# Page12_SOM_Interface.net
KiCad netlist of a schematic drawn in Altium Designer
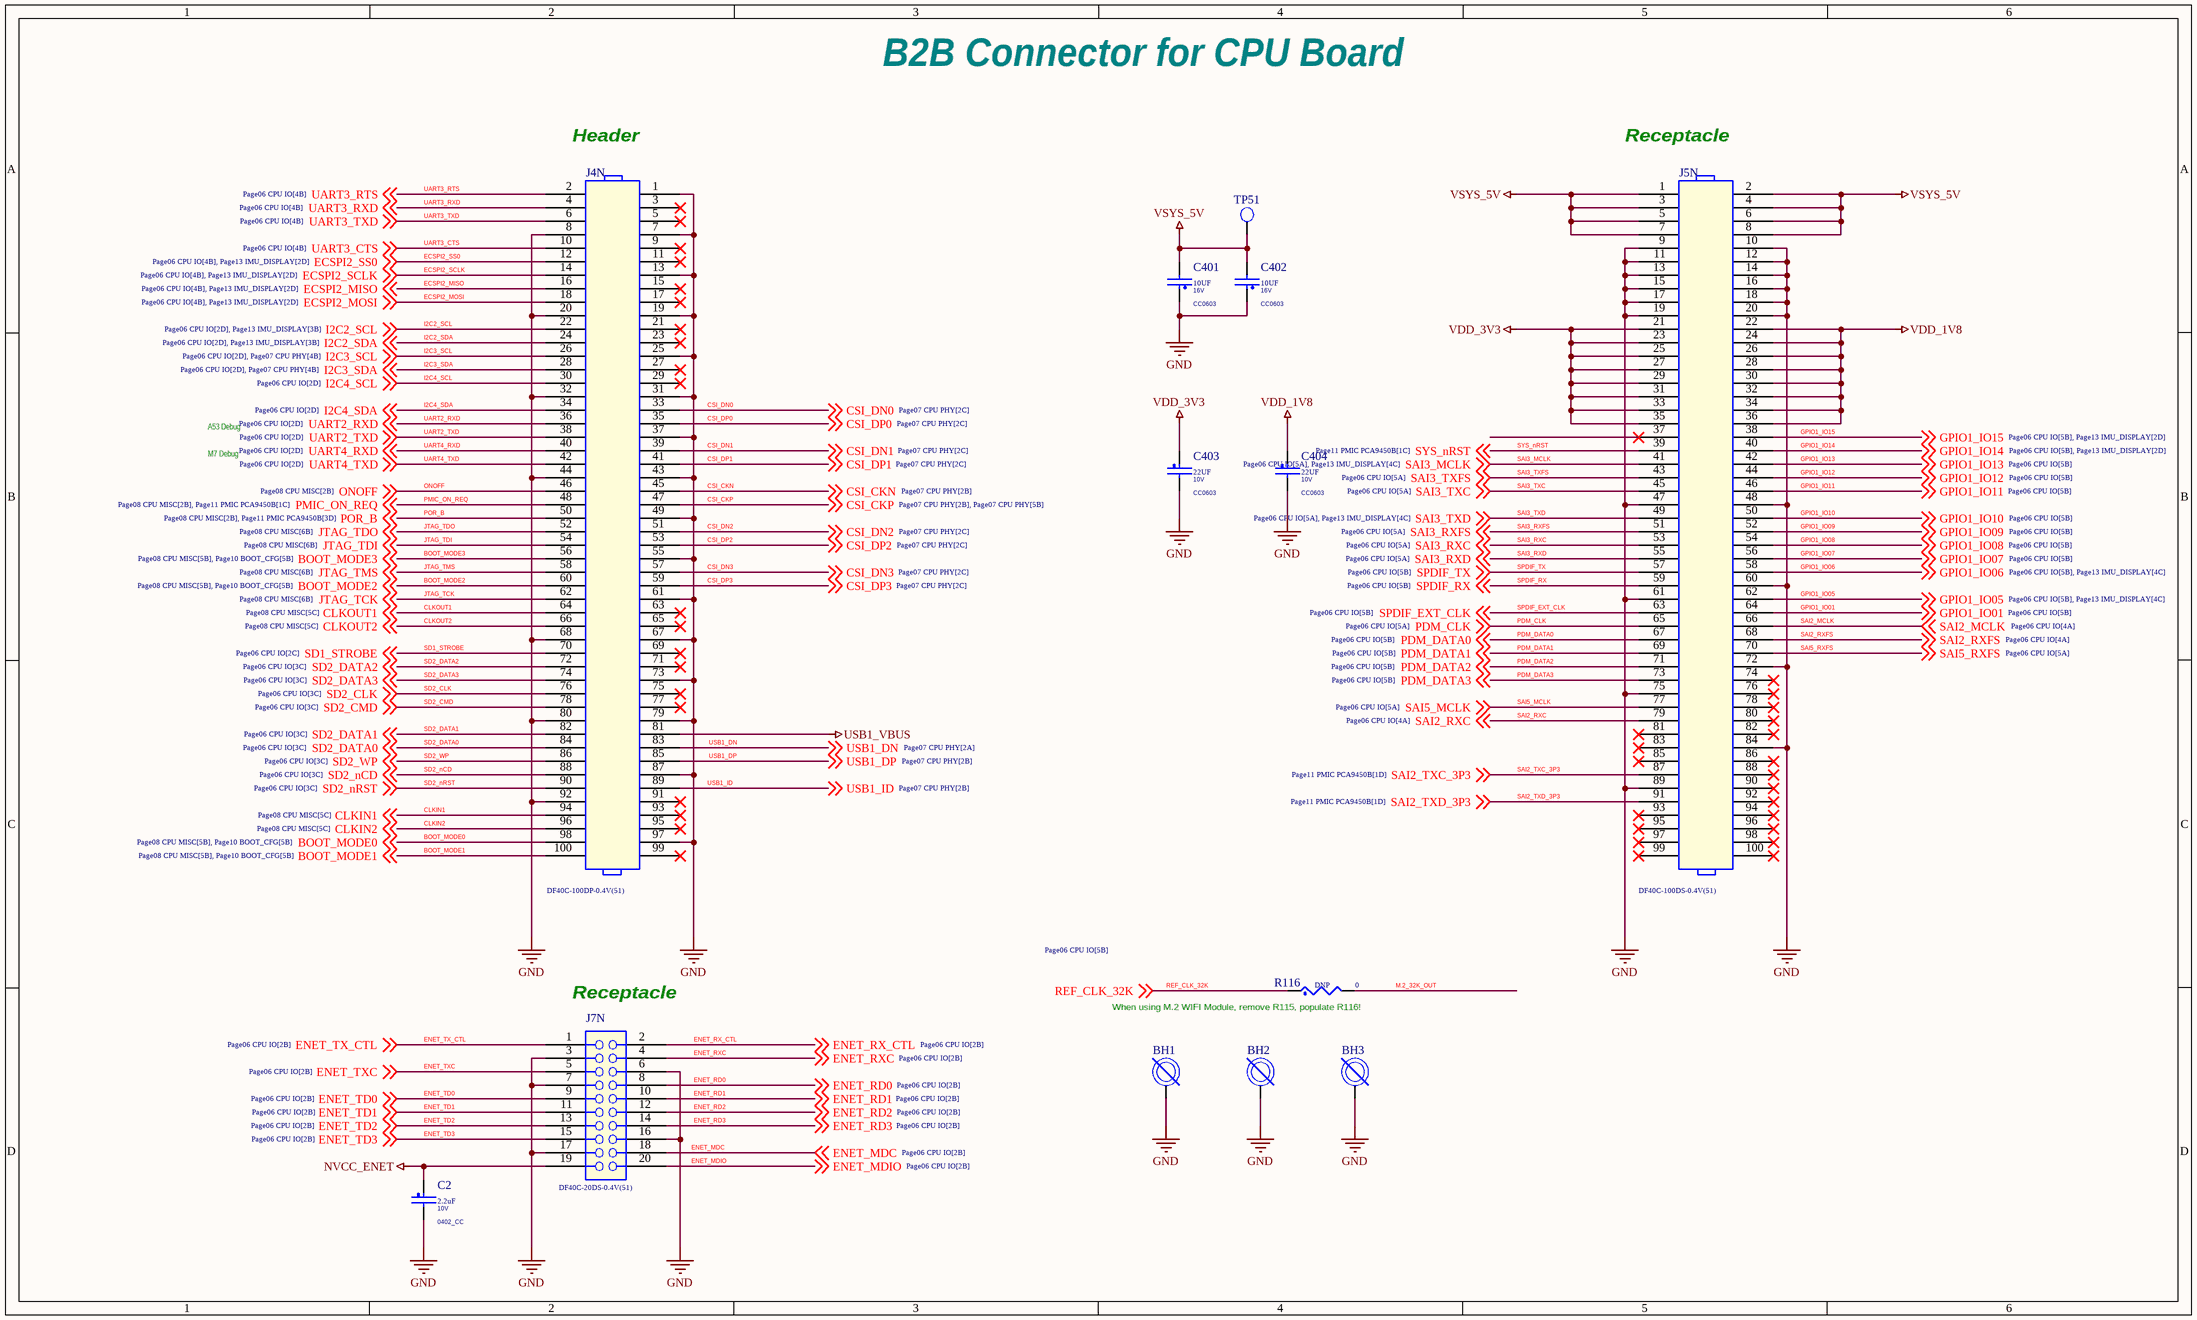
[diagram p0: Page12 SOM Interface.SchDoc]

(export (version "E")
  (design (tool "Eeschema 10.0.6"))
  (components
    (comp (ref "BH1")
      (value "MOUNTING HOLE")
      (footprint "GNDPOINT256")
      (description "MOUNTING HOLE DRILL 109 PAD 200 PLATED TH NO PART TO ORDER")
      (libsource (lib "*") (part "MOUNT_HOLE"))
    )
    (comp (ref "BH2")
      (value "MOUNTING HOLE")
      (footprint "GNDPOINT256")
      (description "MOUNTING HOLE DRILL 109 PAD 200 PLATED TH NO PART TO ORDER")
      (libsource (lib "*") (part "MOUNT_HOLE"))
    )
    (comp (ref "BH3")
      (value "MOUNTING HOLE")
      (footprint "GNDPOINT256")
      (description "MOUNTING HOLE DRILL 109 PAD 200 PLATED TH NO PART TO ORDER")
      (libsource (lib "*") (part "MOUNT_HOLE"))
    )
    (comp (ref "C2")
      (value "2.2uF")
      (footprint "0402_CC")
      (description "CAP CER 2.2uF 10V 10% X5R 0402")
      (fields
        (field (name "TOLERANCE") "10%")
        (field (name "VOLTAGE") "10V")
        (field (name "PCB FOOTPRINT") "0402_CC")
      )
      (libsource (lib "*") (part "CAP_NP"))
    )
    (comp (ref "C401")
      (value "10UF")
      (footprint "0603_CC")
      (description "CAP CER 10.0uF 16V 10% X5R 0603")
      (fields
        (field (name "PCB FOOTPRINT") "CC0603")
        (field (name "TOLERANCE") "10%")
        (field (name "VOLTAGE") "16V")
      )
      (libsource (lib "*") (part "CAP_NP"))
    )
    (comp (ref "C402")
      (value "10UF")
      (footprint "0603_CC")
      (description "CAP CER 10.0uF 16V 10% X5R 0603")
      (fields
        (field (name "PCB FOOTPRINT") "CC0603")
        (field (name "VOLTAGE") "16V")
        (field (name "TOLERANCE") "10%")
      )
      (libsource (lib "*") (part "CAP_NP"))
    )
    (comp (ref "C403")
      (value "22UF")
      (footprint "0603_CC")
      (description "CAP CER 22uF 10V 20% X5R 0603")
      (fields
        (field (name "PCB FOOTPRINT") "CC0603")
        (field (name "VOLTAGE") "10V")
        (field (name "TOLERANCE") "20%")
      )
      (libsource (lib "*") (part "CAP_NP"))
    )
    (comp (ref "C404")
      (value "22UF")
      (footprint "0603_CC")
      (description "CAP CER 22uF 10V 20% X5R 0603")
      (fields
        (field (name "PCB FOOTPRINT") "CC0603")
        (field (name "VOLTAGE") "10V")
        (field (name "TOLERANCE") "20%")
      )
      (libsource (lib "*") (part "CAP_NP"))
    )
    (comp (ref "J4N")
      (value "DF40C-100DP-0.4V(51)")
      (footprint "con100_0p4_21p7x2p05_sm")
      (description "CON 2X50 PLUG SHRD SMT 0.4MM SP 51H AU")
      (libsource (lib "*") (part "HDR_2X50_M"))
    )
    (comp (ref "J5N")
      (value "DF40C-100DS-0.4V(51)")
      (footprint "con100_0p4_22p8x3p1_sm")
      (description "CON 2X50 SKT SHRD SMT 0.4MM SP 65H AU")
      (libsource (lib "") (part "HDR_2X50_M_1"))
    )
    (comp (ref "J7N")
      (value "DF40C-20DS-0.4V(51)")
      (footprint "con20_0p4_6p8x3p1_sm")
      (description "CON 2X10 SKT SHRD SMT 0.4MM SP 63H AU")
      (libsource (lib "*") (part "CONN_HDR_10X2"))
    )
    (comp (ref "R116")
      (value "0")
      (footprint "0402_CC_RES")
      (description "RES MF ZERO OHM 1/16W 5% 0402")
      (fields
        (field (name "ASSY_OPT") "DNP")
        (field (name "VOLTAGE") "1/16W")
        (field (name "TOLERANCE") "5%")
      )
      (libsource (lib "*") (part "RES"))
    )
    (comp (ref "TP51")
      (value "TP_35MIL")
      (footprint "Test Pin")
      (description "TEST POINT PAD .035 SMT, no part to order")
      (libsource (lib "*") (part "T POINT R"))
    )
  )
  (nets
    (net (code "1") (name "/M.2_32K_OUT") (class "Default")
      (node (ref "R116") (pin "2") (pinfunction "2_2") (pintype "passive"))
    )
    (net (code "2") (name "BOOT_MODE0") (class "Default")
      (node (ref "J4N") (pin "98") (pinfunction "98_98") (pintype "passive"))
    )
    (net (code "3") (name "BOOT_MODE1") (class "Default")
      (node (ref "J4N") (pin "100") (pinfunction "100_100") (pintype "passive"))
    )
    (net (code "4") (name "BOOT_MODE2") (class "Default")
      (node (ref "J4N") (pin "60") (pinfunction "60_60") (pintype "passive"))
    )
    (net (code "5") (name "BOOT_MODE3") (class "Default")
      (node (ref "J4N") (pin "56") (pinfunction "56_56") (pintype "passive"))
    )
    (net (code "6") (name "CLKIN1") (class "Default")
      (node (ref "J4N") (pin "94") (pinfunction "94_94") (pintype "passive"))
    )
    (net (code "7") (name "CLKIN2") (class "Default")
      (node (ref "J4N") (pin "96") (pinfunction "96_96") (pintype "passive"))
    )
    (net (code "8") (name "CLKOUT1") (class "Default")
      (node (ref "J4N") (pin "64") (pinfunction "64_64") (pintype "passive"))
    )
    (net (code "9") (name "CLKOUT2") (class "Default")
      (node (ref "J4N") (pin "66") (pinfunction "66_66") (pintype "passive"))
    )
    (net (code "10") (name "CSI_CKN") (class "Default")
      (node (ref "J4N") (pin "45") (pinfunction "45_45") (pintype "passive"))
    )
    (net (code "11") (name "CSI_CKP") (class "Default")
      (node (ref "J4N") (pin "47") (pinfunction "47_47") (pintype "passive"))
    )
    (net (code "12") (name "CSI_DN0") (class "Default")
      (node (ref "J4N") (pin "33") (pinfunction "33_33") (pintype "passive"))
    )
    (net (code "13") (name "CSI_DN1") (class "Default")
      (node (ref "J4N") (pin "39") (pinfunction "39_39") (pintype "passive"))
    )
    (net (code "14") (name "CSI_DN2") (class "Default")
      (node (ref "J4N") (pin "51") (pinfunction "51_51") (pintype "passive"))
    )
    (net (code "15") (name "CSI_DN3") (class "Default")
      (node (ref "J4N") (pin "57") (pinfunction "57_57") (pintype "passive"))
    )
    (net (code "16") (name "CSI_DP0") (class "Default")
      (node (ref "J4N") (pin "35") (pinfunction "35_35") (pintype "passive"))
    )
    (net (code "17") (name "CSI_DP1") (class "Default")
      (node (ref "J4N") (pin "41") (pinfunction "41_41") (pintype "passive"))
    )
    (net (code "18") (name "CSI_DP2") (class "Default")
      (node (ref "J4N") (pin "53") (pinfunction "53_53") (pintype "passive"))
    )
    (net (code "19") (name "CSI_DP3") (class "Default")
      (node (ref "J4N") (pin "59") (pinfunction "59_59") (pintype "passive"))
    )
    (net (code "20") (name "ECSPI2_MISO") (class "Default")
      (node (ref "J4N") (pin "16") (pinfunction "16_16") (pintype "passive"))
    )
    (net (code "21") (name "ECSPI2_MOSI") (class "Default")
      (node (ref "J4N") (pin "18") (pinfunction "18_18") (pintype "passive"))
    )
    (net (code "22") (name "ECSPI2_SCLK") (class "Default")
      (node (ref "J4N") (pin "14") (pinfunction "14_14") (pintype "passive"))
    )
    (net (code "23") (name "ECSPI2_SS0") (class "Default")
      (node (ref "J4N") (pin "12") (pinfunction "12_12") (pintype "passive"))
    )
    (net (code "24") (name "ENET_MDC") (class "Default")
      (node (ref "J7N") (pin "18") (pinfunction "18_18") (pintype "passive"))
    )
    (net (code "25") (name "ENET_MDIO") (class "Default")
      (node (ref "J7N") (pin "20") (pinfunction "20_20") (pintype "passive"))
    )
    (net (code "26") (name "ENET_RD0") (class "Default")
      (node (ref "J7N") (pin "8") (pinfunction "8_8") (pintype "passive"))
    )
    (net (code "27") (name "ENET_RD1") (class "Default")
      (node (ref "J7N") (pin "10") (pinfunction "10_10") (pintype "passive"))
    )
    (net (code "28") (name "ENET_RD2") (class "Default")
      (node (ref "J7N") (pin "12") (pinfunction "12_12") (pintype "passive"))
    )
    (net (code "29") (name "ENET_RD3") (class "Default")
      (node (ref "J7N") (pin "14") (pinfunction "14_14") (pintype "passive"))
    )
    (net (code "30") (name "ENET_RXC") (class "Default")
      (node (ref "J7N") (pin "4") (pinfunction "4_4") (pintype "passive"))
    )
    (net (code "31") (name "ENET_RX_CTL") (class "Default")
      (node (ref "J7N") (pin "2") (pinfunction "2_2") (pintype "passive"))
    )
    (net (code "32") (name "ENET_TD0") (class "Default")
      (node (ref "J7N") (pin "9") (pinfunction "9_9") (pintype "passive"))
    )
    (net (code "33") (name "ENET_TD1") (class "Default")
      (node (ref "J7N") (pin "11") (pinfunction "11_11") (pintype "passive"))
    )
    (net (code "34") (name "ENET_TD2") (class "Default")
      (node (ref "J7N") (pin "13") (pinfunction "13_13") (pintype "passive"))
    )
    (net (code "35") (name "ENET_TD3") (class "Default")
      (node (ref "J7N") (pin "15") (pinfunction "15_15") (pintype "passive"))
    )
    (net (code "36") (name "ENET_TXC") (class "Default")
      (node (ref "J7N") (pin "5") (pinfunction "5_5") (pintype "passive"))
    )
    (net (code "37") (name "ENET_TX_CTL") (class "Default")
      (node (ref "J7N") (pin "1") (pinfunction "1_1") (pintype "passive"))
    )
    (net (code "38") (name "GND") (class "Default")
      (node (ref "BH1") (pin "1") (pinfunction "1_1") (pintype "passive"))
      (node (ref "BH2") (pin "1") (pinfunction "1_1") (pintype "passive"))
      (node (ref "BH3") (pin "1") (pinfunction "1_1") (pintype "passive"))
      (node (ref "C2") (pin "2") (pinfunction "2_2") (pintype "passive"))
      (node (ref "C401") (pin "1") (pinfunction "1_1") (pintype "passive"))
      (node (ref "C402") (pin "1") (pinfunction "1_1") (pintype "passive"))
      (node (ref "C403") (pin "2") (pinfunction "2_2") (pintype "passive"))
      (node (ref "C404") (pin "2") (pinfunction "2_2") (pintype "passive"))
      (node (ref "J4N") (pin "1") (pinfunction "1_1") (pintype "passive"))
      (node (ref "J4N") (pin "13") (pinfunction "13_13") (pintype "passive"))
      (node (ref "J4N") (pin "19") (pinfunction "19_19") (pintype "passive"))
      (node (ref "J4N") (pin "20") (pinfunction "20_20") (pintype "passive"))
      (node (ref "J4N") (pin "25") (pinfunction "25_25") (pintype "passive"))
      (node (ref "J4N") (pin "31") (pinfunction "31_31") (pintype "passive"))
      (node (ref "J4N") (pin "32") (pinfunction "32_32") (pintype "passive"))
      (node (ref "J4N") (pin "37") (pinfunction "37_37") (pintype "passive"))
      (node (ref "J4N") (pin "43") (pinfunction "43_43") (pintype "passive"))
      (node (ref "J4N") (pin "44") (pinfunction "44_44") (pintype "passive"))
      (node (ref "J4N") (pin "49") (pinfunction "49_49") (pintype "passive"))
      (node (ref "J4N") (pin "55") (pinfunction "55_55") (pintype "passive"))
      (node (ref "J4N") (pin "61") (pinfunction "61_61") (pintype "passive"))
      (node (ref "J4N") (pin "67") (pinfunction "67_67") (pintype "passive"))
      (node (ref "J4N") (pin "68") (pinfunction "68_68") (pintype "passive"))
      (node (ref "J4N") (pin "7") (pinfunction "7_7") (pintype "passive"))
      (node (ref "J4N") (pin "73") (pinfunction "73_73") (pintype "passive"))
      (node (ref "J4N") (pin "79") (pinfunction "79_79") (pintype "passive"))
      (node (ref "J4N") (pin "8") (pinfunction "8_8") (pintype "passive"))
      (node (ref "J4N") (pin "80") (pinfunction "80_80") (pintype "passive"))
      (node (ref "J4N") (pin "87") (pinfunction "87_87") (pintype "passive"))
      (node (ref "J4N") (pin "92") (pinfunction "92_92") (pintype "passive"))
      (node (ref "J4N") (pin "97") (pinfunction "97_97") (pintype "passive"))
      (node (ref "J5N") (pin "10") (pinfunction "10_10") (pintype "passive"))
      (node (ref "J5N") (pin "11") (pinfunction "11_11") (pintype "passive"))
      (node (ref "J5N") (pin "12") (pinfunction "12_12") (pintype "passive"))
      (node (ref "J5N") (pin "13") (pinfunction "13_13") (pintype "passive"))
      (node (ref "J5N") (pin "14") (pinfunction "14_14") (pintype "passive"))
      (node (ref "J5N") (pin "15") (pinfunction "15_15") (pintype "passive"))
      (node (ref "J5N") (pin "16") (pinfunction "16_16") (pintype "passive"))
      (node (ref "J5N") (pin "17") (pinfunction "17_17") (pintype "passive"))
      (node (ref "J5N") (pin "18") (pinfunction "18_18") (pintype "passive"))
      (node (ref "J5N") (pin "19") (pinfunction "19_19") (pintype "passive"))
      (node (ref "J5N") (pin "20") (pinfunction "20_20") (pintype "passive"))
      (node (ref "J5N") (pin "47") (pinfunction "47_47") (pintype "passive"))
      (node (ref "J5N") (pin "48") (pinfunction "48_48") (pintype "passive"))
      (node (ref "J5N") (pin "60") (pinfunction "60_60") (pintype "passive"))
      (node (ref "J5N") (pin "61") (pinfunction "61_61") (pintype "passive"))
      (node (ref "J5N") (pin "72") (pinfunction "72_72") (pintype "passive"))
      (node (ref "J5N") (pin "75") (pinfunction "75_75") (pintype "passive"))
      (node (ref "J5N") (pin "84") (pinfunction "84_84") (pintype "passive"))
      (node (ref "J5N") (pin "89") (pinfunction "89_89") (pintype "passive"))
      (node (ref "J5N") (pin "9") (pinfunction "9_9") (pintype "passive"))
      (node (ref "J7N") (pin "16") (pinfunction "16_16") (pintype "passive"))
      (node (ref "J7N") (pin "17") (pinfunction "17_17") (pintype "passive"))
      (node (ref "J7N") (pin "3") (pinfunction "3_3") (pintype "passive"))
      (node (ref "J7N") (pin "6") (pinfunction "6_6") (pintype "passive"))
      (node (ref "J7N") (pin "7") (pinfunction "7_7") (pintype "passive"))
    )
    (net (code "39") (name "GPIO1_IO01") (class "Default")
      (node (ref "J5N") (pin "64") (pinfunction "64_64") (pintype "passive"))
    )
    (net (code "40") (name "GPIO1_IO05") (class "Default")
      (node (ref "J5N") (pin "62") (pinfunction "62_62") (pintype "passive"))
    )
    (net (code "41") (name "GPIO1_IO06") (class "Default")
      (node (ref "J5N") (pin "58") (pinfunction "58_58") (pintype "passive"))
    )
    (net (code "42") (name "GPIO1_IO07") (class "Default")
      (node (ref "J5N") (pin "56") (pinfunction "56_56") (pintype "passive"))
    )
    (net (code "43") (name "GPIO1_IO08") (class "Default")
      (node (ref "J5N") (pin "54") (pinfunction "54_54") (pintype "passive"))
    )
    (net (code "44") (name "GPIO1_IO09") (class "Default")
      (node (ref "J5N") (pin "52") (pinfunction "52_52") (pintype "passive"))
    )
    (net (code "45") (name "GPIO1_IO10") (class "Default")
      (node (ref "J5N") (pin "50") (pinfunction "50_50") (pintype "passive"))
    )
    (net (code "46") (name "GPIO1_IO11") (class "Default")
      (node (ref "J5N") (pin "46") (pinfunction "46_46") (pintype "passive"))
    )
    (net (code "47") (name "GPIO1_IO12") (class "Default")
      (node (ref "J5N") (pin "44") (pinfunction "44_44") (pintype "passive"))
    )
    (net (code "48") (name "GPIO1_IO13") (class "Default")
      (node (ref "J5N") (pin "42") (pinfunction "42_42") (pintype "passive"))
    )
    (net (code "49") (name "GPIO1_IO14") (class "Default")
      (node (ref "J5N") (pin "40") (pinfunction "40_40") (pintype "passive"))
    )
    (net (code "50") (name "GPIO1_IO15") (class "Default")
      (node (ref "J5N") (pin "38") (pinfunction "38_38") (pintype "passive"))
    )
    (net (code "51") (name "I2C2_SCL") (class "Default")
      (node (ref "J4N") (pin "22") (pinfunction "22_22") (pintype "passive"))
    )
    (net (code "52") (name "I2C2_SDA") (class "Default")
      (node (ref "J4N") (pin "24") (pinfunction "24_24") (pintype "passive"))
    )
    (net (code "53") (name "I2C3_SCL") (class "Default")
      (node (ref "J4N") (pin "26") (pinfunction "26_26") (pintype "passive"))
    )
    (net (code "54") (name "I2C3_SDA") (class "Default")
      (node (ref "J4N") (pin "28") (pinfunction "28_28") (pintype "passive"))
    )
    (net (code "55") (name "I2C4_SCL") (class "Default")
      (node (ref "J4N") (pin "30") (pinfunction "30_30") (pintype "passive"))
    )
    (net (code "56") (name "I2C4_SDA") (class "Default")
      (node (ref "J4N") (pin "34") (pinfunction "34_34") (pintype "passive"))
    )
    (net (code "57") (name "JTAG_TCK") (class "Default")
      (node (ref "J4N") (pin "62") (pinfunction "62_62") (pintype "passive"))
    )
    (net (code "58") (name "JTAG_TDI") (class "Default")
      (node (ref "J4N") (pin "54") (pinfunction "54_54") (pintype "passive"))
    )
    (net (code "59") (name "JTAG_TDO") (class "Default")
      (node (ref "J4N") (pin "52") (pinfunction "52_52") (pintype "passive"))
    )
    (net (code "60") (name "JTAG_TMS") (class "Default")
      (node (ref "J4N") (pin "58") (pinfunction "58_58") (pintype "passive"))
    )
    (net (code "61") (name "NVCC_ENET") (class "Default")
      (node (ref "C2") (pin "1") (pinfunction "1_1") (pintype "passive"))
      (node (ref "J7N") (pin "19") (pinfunction "19_19") (pintype "passive"))
    )
    (net (code "62") (name "ONOFF") (class "Default")
      (node (ref "J4N") (pin "46") (pinfunction "46_46") (pintype "passive"))
    )
    (net (code "63") (name "PDM_CLK") (class "Default")
      (node (ref "J5N") (pin "65") (pinfunction "65_65") (pintype "passive"))
    )
    (net (code "64") (name "PDM_DATA0") (class "Default")
      (node (ref "J5N") (pin "67") (pinfunction "67_67") (pintype "passive"))
    )
    (net (code "65") (name "PDM_DATA1") (class "Default")
      (node (ref "J5N") (pin "69") (pinfunction "69_69") (pintype "passive"))
    )
    (net (code "66") (name "PDM_DATA2") (class "Default")
      (node (ref "J5N") (pin "71") (pinfunction "71_71") (pintype "passive"))
    )
    (net (code "67") (name "PDM_DATA3") (class "Default")
      (node (ref "J5N") (pin "73") (pinfunction "73_73") (pintype "passive"))
    )
    (net (code "68") (name "PMIC_ON_REQ") (class "Default")
      (node (ref "J4N") (pin "48") (pinfunction "48_48") (pintype "passive"))
    )
    (net (code "69") (name "POR_B") (class "Default")
      (node (ref "J4N") (pin "50") (pinfunction "50_50") (pintype "passive"))
    )
    (net (code "70") (name "REF_CLK_32K") (class "Default")
      (node (ref "R116") (pin "1") (pinfunction "1_1") (pintype "passive"))
    )
    (net (code "71") (name "SAI2_MCLK") (class "Default")
      (node (ref "J5N") (pin "66") (pinfunction "66_66") (pintype "passive"))
    )
    (net (code "72") (name "SAI2_RXC") (class "Default")
      (node (ref "J5N") (pin "79") (pinfunction "79_79") (pintype "passive"))
    )
    (net (code "73") (name "SAI2_RXFS") (class "Default")
      (node (ref "J5N") (pin "68") (pinfunction "68_68") (pintype "passive"))
    )
    (net (code "74") (name "SAI2_TXC_3P3") (class "Default")
      (node (ref "J5N") (pin "87") (pinfunction "87_87") (pintype "passive"))
    )
    (net (code "75") (name "SAI2_TXD_3P3") (class "Default")
      (node (ref "J5N") (pin "91") (pinfunction "91_91") (pintype "passive"))
    )
    (net (code "76") (name "SAI3_MCLK") (class "Default")
      (node (ref "J5N") (pin "41") (pinfunction "41_41") (pintype "passive"))
    )
    (net (code "77") (name "SAI3_RXC") (class "Default")
      (node (ref "J5N") (pin "53") (pinfunction "53_53") (pintype "passive"))
    )
    (net (code "78") (name "SAI3_RXD") (class "Default")
      (node (ref "J5N") (pin "55") (pinfunction "55_55") (pintype "passive"))
    )
    (net (code "79") (name "SAI3_RXFS") (class "Default")
      (node (ref "J5N") (pin "51") (pinfunction "51_51") (pintype "passive"))
    )
    (net (code "80") (name "SAI3_TXC") (class "Default")
      (node (ref "J5N") (pin "45") (pinfunction "45_45") (pintype "passive"))
    )
    (net (code "81") (name "SAI3_TXD") (class "Default")
      (node (ref "J5N") (pin "49") (pinfunction "49_49") (pintype "passive"))
    )
    (net (code "82") (name "SAI3_TXFS") (class "Default")
      (node (ref "J5N") (pin "43") (pinfunction "43_43") (pintype "passive"))
    )
    (net (code "83") (name "SAI5_MCLK") (class "Default")
      (node (ref "J5N") (pin "77") (pinfunction "77_77") (pintype "passive"))
    )
    (net (code "84") (name "SAI5_RXFS") (class "Default")
      (node (ref "J5N") (pin "70") (pinfunction "70_70") (pintype "passive"))
    )
    (net (code "85") (name "SD1_STROBE") (class "Default")
      (node (ref "J4N") (pin "70") (pinfunction "70_70") (pintype "passive"))
    )
    (net (code "86") (name "SD2_CLK") (class "Default")
      (node (ref "J4N") (pin "76") (pinfunction "76_76") (pintype "passive"))
    )
    (net (code "87") (name "SD2_CMD") (class "Default")
      (node (ref "J4N") (pin "78") (pinfunction "78_78") (pintype "passive"))
    )
    (net (code "88") (name "SD2_DATA0") (class "Default")
      (node (ref "J4N") (pin "84") (pinfunction "84_84") (pintype "passive"))
    )
    (net (code "89") (name "SD2_DATA1") (class "Default")
      (node (ref "J4N") (pin "82") (pinfunction "82_82") (pintype "passive"))
    )
    (net (code "90") (name "SD2_DATA2") (class "Default")
      (node (ref "J4N") (pin "72") (pinfunction "72_72") (pintype "passive"))
    )
    (net (code "91") (name "SD2_DATA3") (class "Default")
      (node (ref "J4N") (pin "74") (pinfunction "74_74") (pintype "passive"))
    )
    (net (code "92") (name "SD2_WP") (class "Default")
      (node (ref "J4N") (pin "86") (pinfunction "86_86") (pintype "passive"))
    )
    (net (code "93") (name "SD2_nCD") (class "Default")
      (node (ref "J4N") (pin "88") (pinfunction "88_88") (pintype "passive"))
    )
    (net (code "94") (name "SD2_nRST") (class "Default")
      (node (ref "J4N") (pin "90") (pinfunction "90_90") (pintype "passive"))
    )
    (net (code "95") (name "SPDIF_EXT_CLK") (class "Default")
      (node (ref "J5N") (pin "63") (pinfunction "63_63") (pintype "passive"))
    )
    (net (code "96") (name "SPDIF_RX") (class "Default")
      (node (ref "J5N") (pin "59") (pinfunction "59_59") (pintype "passive"))
    )
    (net (code "97") (name "SPDIF_TX") (class "Default")
      (node (ref "J5N") (pin "57") (pinfunction "57_57") (pintype "passive"))
    )
    (net (code "98") (name "SYS_nRST") (class "Default")
      (node (ref "J5N") (pin "39") (pinfunction "39_39") (pintype "passive"))
    )
    (net (code "99") (name "UART2_RXD") (class "Default")
      (node (ref "J4N") (pin "36") (pinfunction "36_36") (pintype "passive"))
    )
    (net (code "100") (name "UART2_TXD") (class "Default")
      (node (ref "J4N") (pin "38") (pinfunction "38_38") (pintype "passive"))
    )
    (net (code "101") (name "UART3_CTS") (class "Default")
      (node (ref "J4N") (pin "10") (pinfunction "10_10") (pintype "passive"))
    )
    (net (code "102") (name "UART3_RTS") (class "Default")
      (node (ref "J4N") (pin "2") (pinfunction "2_2") (pintype "passive"))
    )
    (net (code "103") (name "UART3_RXD") (class "Default")
      (node (ref "J4N") (pin "4") (pinfunction "4_4") (pintype "passive"))
    )
    (net (code "104") (name "UART3_TXD") (class "Default")
      (node (ref "J4N") (pin "6") (pinfunction "6_6") (pintype "passive"))
    )
    (net (code "105") (name "UART4_RXD") (class "Default")
      (node (ref "J4N") (pin "40") (pinfunction "40_40") (pintype "passive"))
    )
    (net (code "106") (name "UART4_TXD") (class "Default")
      (node (ref "J4N") (pin "42") (pinfunction "42_42") (pintype "passive"))
    )
    (net (code "107") (name "USB1_DN") (class "Default")
      (node (ref "J4N") (pin "83") (pinfunction "83_83") (pintype "passive"))
    )
    (net (code "108") (name "USB1_DP") (class "Default")
      (node (ref "J4N") (pin "85") (pinfunction "85_85") (pintype "passive"))
    )
    (net (code "109") (name "USB1_ID") (class "Default")
      (node (ref "J4N") (pin "89") (pinfunction "89_89") (pintype "passive"))
    )
    (net (code "110") (name "USB1_VBUS") (class "Default")
      (node (ref "J4N") (pin "81") (pinfunction "81_81") (pintype "passive"))
    )
    (net (code "111") (name "VDD_1V8") (class "Default")
      (node (ref "C404") (pin "1") (pinfunction "1_1") (pintype "passive"))
      (node (ref "J5N") (pin "22") (pinfunction "22_22") (pintype "passive"))
      (node (ref "J5N") (pin "24") (pinfunction "24_24") (pintype "passive"))
      (node (ref "J5N") (pin "26") (pinfunction "26_26") (pintype "passive"))
      (node (ref "J5N") (pin "28") (pinfunction "28_28") (pintype "passive"))
      (node (ref "J5N") (pin "30") (pinfunction "30_30") (pintype "passive"))
      (node (ref "J5N") (pin "32") (pinfunction "32_32") (pintype "passive"))
      (node (ref "J5N") (pin "34") (pinfunction "34_34") (pintype "passive"))
      (node (ref "J5N") (pin "36") (pinfunction "36_36") (pintype "passive"))
    )
    (net (code "112") (name "VDD_3V3") (class "Default")
      (node (ref "C403") (pin "1") (pinfunction "1_1") (pintype "passive"))
      (node (ref "J5N") (pin "21") (pinfunction "21_21") (pintype "passive"))
      (node (ref "J5N") (pin "23") (pinfunction "23_23") (pintype "passive"))
      (node (ref "J5N") (pin "25") (pinfunction "25_25") (pintype "passive"))
      (node (ref "J5N") (pin "27") (pinfunction "27_27") (pintype "passive"))
      (node (ref "J5N") (pin "29") (pinfunction "29_29") (pintype "passive"))
      (node (ref "J5N") (pin "31") (pinfunction "31_31") (pintype "passive"))
      (node (ref "J5N") (pin "33") (pinfunction "33_33") (pintype "passive"))
      (node (ref "J5N") (pin "35") (pinfunction "35_35") (pintype "passive"))
    )
    (net (code "113") (name "VSYS_5V") (class "Default")
      (node (ref "C401") (pin "2") (pinfunction "2_2") (pintype "passive"))
      (node (ref "C402") (pin "2") (pinfunction "2_2") (pintype "passive"))
      (node (ref "J5N") (pin "1") (pinfunction "1_1") (pintype "passive"))
      (node (ref "J5N") (pin "2") (pinfunction "2_2") (pintype "passive"))
      (node (ref "J5N") (pin "3") (pinfunction "3_3") (pintype "passive"))
      (node (ref "J5N") (pin "4") (pinfunction "4_4") (pintype "passive"))
      (node (ref "J5N") (pin "5") (pinfunction "5_5") (pintype "passive"))
      (node (ref "J5N") (pin "6") (pinfunction "6_6") (pintype "passive"))
      (node (ref "J5N") (pin "7") (pinfunction "7_7") (pintype "passive"))
      (node (ref "J5N") (pin "8") (pinfunction "8_8") (pintype "passive"))
      (node (ref "TP51") (pin "1") (pinfunction "TP_1") (pintype "passive"))
    )
    (net (code "114") (name "unconnected-(J4N-Pad3)") (class "Default")
      (node (ref "J4N") (pin "3") (pinfunction "3_3") (pintype "passive+no_connect"))
    )
    (net (code "115") (name "unconnected-(J4N-Pad5)") (class "Default")
      (node (ref "J4N") (pin "5") (pinfunction "5_5") (pintype "passive+no_connect"))
    )
    (net (code "116") (name "unconnected-(J4N-Pad9)") (class "Default")
      (node (ref "J4N") (pin "9") (pinfunction "9_9") (pintype "passive+no_connect"))
    )
    (net (code "117") (name "unconnected-(J4N-Pad11)") (class "Default")
      (node (ref "J4N") (pin "11") (pinfunction "11_11") (pintype "passive+no_connect"))
    )
    (net (code "118") (name "unconnected-(J4N-Pad15)") (class "Default")
      (node (ref "J4N") (pin "15") (pinfunction "15_15") (pintype "passive+no_connect"))
    )
    (net (code "119") (name "unconnected-(J4N-Pad17)") (class "Default")
      (node (ref "J4N") (pin "17") (pinfunction "17_17") (pintype "passive+no_connect"))
    )
    (net (code "120") (name "unconnected-(J4N-Pad21)") (class "Default")
      (node (ref "J4N") (pin "21") (pinfunction "21_21") (pintype "passive+no_connect"))
    )
    (net (code "121") (name "unconnected-(J4N-Pad23)") (class "Default")
      (node (ref "J4N") (pin "23") (pinfunction "23_23") (pintype "passive+no_connect"))
    )
    (net (code "122") (name "unconnected-(J4N-Pad27)") (class "Default")
      (node (ref "J4N") (pin "27") (pinfunction "27_27") (pintype "passive+no_connect"))
    )
    (net (code "123") (name "unconnected-(J4N-Pad29)") (class "Default")
      (node (ref "J4N") (pin "29") (pinfunction "29_29") (pintype "passive+no_connect"))
    )
    (net (code "124") (name "unconnected-(J4N-Pad63)") (class "Default")
      (node (ref "J4N") (pin "63") (pinfunction "63_63") (pintype "passive+no_connect"))
    )
    (net (code "125") (name "unconnected-(J4N-Pad65)") (class "Default")
      (node (ref "J4N") (pin "65") (pinfunction "65_65") (pintype "passive+no_connect"))
    )
    (net (code "126") (name "unconnected-(J4N-Pad69)") (class "Default")
      (node (ref "J4N") (pin "69") (pinfunction "69_69") (pintype "passive+no_connect"))
    )
    (net (code "127") (name "unconnected-(J4N-Pad71)") (class "Default")
      (node (ref "J4N") (pin "71") (pinfunction "71_71") (pintype "passive+no_connect"))
    )
    (net (code "128") (name "unconnected-(J4N-Pad75)") (class "Default")
      (node (ref "J4N") (pin "75") (pinfunction "75_75") (pintype "passive+no_connect"))
    )
    (net (code "129") (name "unconnected-(J4N-Pad77)") (class "Default")
      (node (ref "J4N") (pin "77") (pinfunction "77_77") (pintype "passive+no_connect"))
    )
    (net (code "130") (name "unconnected-(J4N-Pad91)") (class "Default")
      (node (ref "J4N") (pin "91") (pinfunction "91_91") (pintype "passive+no_connect"))
    )
    (net (code "131") (name "unconnected-(J4N-Pad93)") (class "Default")
      (node (ref "J4N") (pin "93") (pinfunction "93_93") (pintype "passive+no_connect"))
    )
    (net (code "132") (name "unconnected-(J4N-Pad95)") (class "Default")
      (node (ref "J4N") (pin "95") (pinfunction "95_95") (pintype "passive+no_connect"))
    )
    (net (code "133") (name "unconnected-(J4N-Pad99)") (class "Default")
      (node (ref "J4N") (pin "99") (pinfunction "99_99") (pintype "passive+no_connect"))
    )
    (net (code "134") (name "unconnected-(J5N-Pad37)") (class "Default")
      (node (ref "J5N") (pin "37") (pinfunction "37_37") (pintype "passive+no_connect"))
    )
    (net (code "135") (name "unconnected-(J5N-Pad74)") (class "Default")
      (node (ref "J5N") (pin "74") (pinfunction "74_74") (pintype "passive+no_connect"))
    )
    (net (code "136") (name "unconnected-(J5N-Pad76)") (class "Default")
      (node (ref "J5N") (pin "76") (pinfunction "76_76") (pintype "passive+no_connect"))
    )
    (net (code "137") (name "unconnected-(J5N-Pad78)") (class "Default")
      (node (ref "J5N") (pin "78") (pinfunction "78_78") (pintype "passive+no_connect"))
    )
    (net (code "138") (name "unconnected-(J5N-Pad80)") (class "Default")
      (node (ref "J5N") (pin "80") (pinfunction "80_80") (pintype "passive+no_connect"))
    )
    (net (code "139") (name "unconnected-(J5N-Pad81)") (class "Default")
      (node (ref "J5N") (pin "81") (pinfunction "81_81") (pintype "passive+no_connect"))
    )
    (net (code "140") (name "unconnected-(J5N-Pad82)") (class "Default")
      (node (ref "J5N") (pin "82") (pinfunction "82_82") (pintype "passive+no_connect"))
    )
    (net (code "141") (name "unconnected-(J5N-Pad83)") (class "Default")
      (node (ref "J5N") (pin "83") (pinfunction "83_83") (pintype "passive+no_connect"))
    )
    (net (code "142") (name "unconnected-(J5N-Pad85)") (class "Default")
      (node (ref "J5N") (pin "85") (pinfunction "85_85") (pintype "passive+no_connect"))
    )
    (net (code "143") (name "unconnected-(J5N-Pad86)") (class "Default")
      (node (ref "J5N") (pin "86") (pinfunction "86_86") (pintype "passive+no_connect"))
    )
    (net (code "144") (name "unconnected-(J5N-Pad88)") (class "Default")
      (node (ref "J5N") (pin "88") (pinfunction "88_88") (pintype "passive+no_connect"))
    )
    (net (code "145") (name "unconnected-(J5N-Pad90)") (class "Default")
      (node (ref "J5N") (pin "90") (pinfunction "90_90") (pintype "passive+no_connect"))
    )
    (net (code "146") (name "unconnected-(J5N-Pad92)") (class "Default")
      (node (ref "J5N") (pin "92") (pinfunction "92_92") (pintype "passive+no_connect"))
    )
    (net (code "147") (name "unconnected-(J5N-Pad93)") (class "Default")
      (node (ref "J5N") (pin "93") (pinfunction "93_93") (pintype "passive+no_connect"))
    )
    (net (code "148") (name "unconnected-(J5N-Pad94)") (class "Default")
      (node (ref "J5N") (pin "94") (pinfunction "94_94") (pintype "passive+no_connect"))
    )
    (net (code "149") (name "unconnected-(J5N-Pad95)") (class "Default")
      (node (ref "J5N") (pin "95") (pinfunction "95_95") (pintype "passive+no_connect"))
    )
    (net (code "150") (name "unconnected-(J5N-Pad96)") (class "Default")
      (node (ref "J5N") (pin "96") (pinfunction "96_96") (pintype "passive+no_connect"))
    )
    (net (code "151") (name "unconnected-(J5N-Pad97)") (class "Default")
      (node (ref "J5N") (pin "97") (pinfunction "97_97") (pintype "passive+no_connect"))
    )
    (net (code "152") (name "unconnected-(J5N-Pad98)") (class "Default")
      (node (ref "J5N") (pin "98") (pinfunction "98_98") (pintype "passive+no_connect"))
    )
    (net (code "153") (name "unconnected-(J5N-Pad99)") (class "Default")
      (node (ref "J5N") (pin "99") (pinfunction "99_99") (pintype "passive+no_connect"))
    )
    (net (code "154") (name "unconnected-(J5N-Pad100)") (class "Default")
      (node (ref "J5N") (pin "100") (pinfunction "100_100") (pintype "passive+no_connect"))
    )
  )
)
